# 555_Astable_2.net
KiCad netlist of a schematic drawn in EAGLE
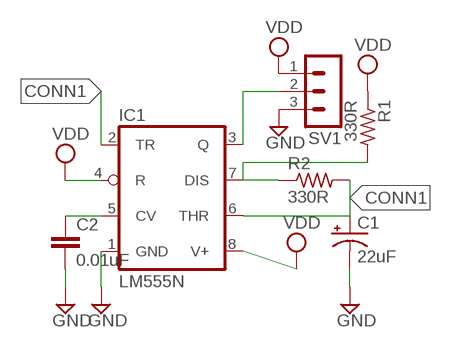
[diagram p0: schematic, sheet 1]

(export (version "E")
  (design (tool "Eeschema 10.0.6"))
  (components
    (comp (ref "C1")
      (value "22uF")
      (footprint "eagle-import:E1,8-4")
      (libsource (lib "eagle-import") (part "CPOL-USE1.8-4"))
    )
    (comp (ref "C2")
      (value "0.01uF")
      (footprint "eagle-import:C050-024X044")
      (libsource (lib "eagle-import") (part "C-EU050-024X044"))
    )
    (comp (ref "IC1")
      (value "LM555N")
      (footprint "eagle-import:DIL08")
      (libsource (lib "eagle-import") (part "555NLM"))
    )
    (comp (ref "R1")
      (value "330R")
      (footprint "eagle-import:0207_10")
      (libsource (lib "eagle-import") (part "R-US_0207/10"))
    )
    (comp (ref "R2")
      (value "330R")
      (footprint "eagle-import:0207_10")
      (libsource (lib "eagle-import") (part "R-US_0207/10"))
    )
    (comp (ref "SV1")
      (value "MA03-1")
      (footprint "eagle-import:MA03-1")
      (libsource (lib "eagle-import") (part "MA03-1"))
    )
  )
  (nets
    (net (code "1") (name "CONN1") (class "Default")
      (node (ref "C1") (pin "+") (pinfunction "+_+") (pintype "passive"))
      (node (ref "IC1") (pin "2") (pinfunction "TR_2") (pintype "input"))
      (node (ref "IC1") (pin "6") (pinfunction "THR_6") (pintype "input"))
      (node (ref "R2") (pin "2") (pinfunction "2_2") (pintype "passive"))
    )
    (net (code "2") (name "GND") (class "Default")
      (node (ref "C1") (pin "-") (pinfunction "-_-") (pintype "passive"))
      (node (ref "C2") (pin "2") (pinfunction "2_2") (pintype "passive"))
      (node (ref "IC1") (pin "1") (pinfunction "GND_1") (pintype "power_in"))
      (node (ref "SV1") (pin "3") (pinfunction "3_3") (pintype "passive"))
    )
    (net (code "3") (name "Net-(IC1-CV)") (class "Default")
      (node (ref "C2") (pin "1") (pinfunction "1_1") (pintype "passive"))
      (node (ref "IC1") (pin "5") (pinfunction "CV_5") (pintype "input"))
    )
    (net (code "4") (name "Net-(IC1-DIS)") (class "Default")
      (node (ref "IC1") (pin "7") (pinfunction "DIS_7") (pintype "input"))
      (node (ref "R1") (pin "2") (pinfunction "2_2") (pintype "passive"))
      (node (ref "R2") (pin "1") (pinfunction "1_1") (pintype "passive"))
    )
    (net (code "5") (name "Net-(IC1-Q)") (class "Default")
      (node (ref "IC1") (pin "3") (pinfunction "Q_3") (pintype "output"))
      (node (ref "SV1") (pin "2") (pinfunction "2_2") (pintype "passive"))
    )
    (net (code "6") (name "VDD") (class "Default")
      (node (ref "IC1") (pin "4") (pinfunction "R_4") (pintype "input"))
      (node (ref "IC1") (pin "8") (pinfunction "V+_8") (pintype "power_in"))
      (node (ref "R1") (pin "1") (pinfunction "1_1") (pintype "passive"))
      (node (ref "SV1") (pin "1") (pinfunction "1_1") (pintype "passive"))
    )
  )
)
